# fpga-power.net
KiCad netlist of a schematic drawn in Altium Designer
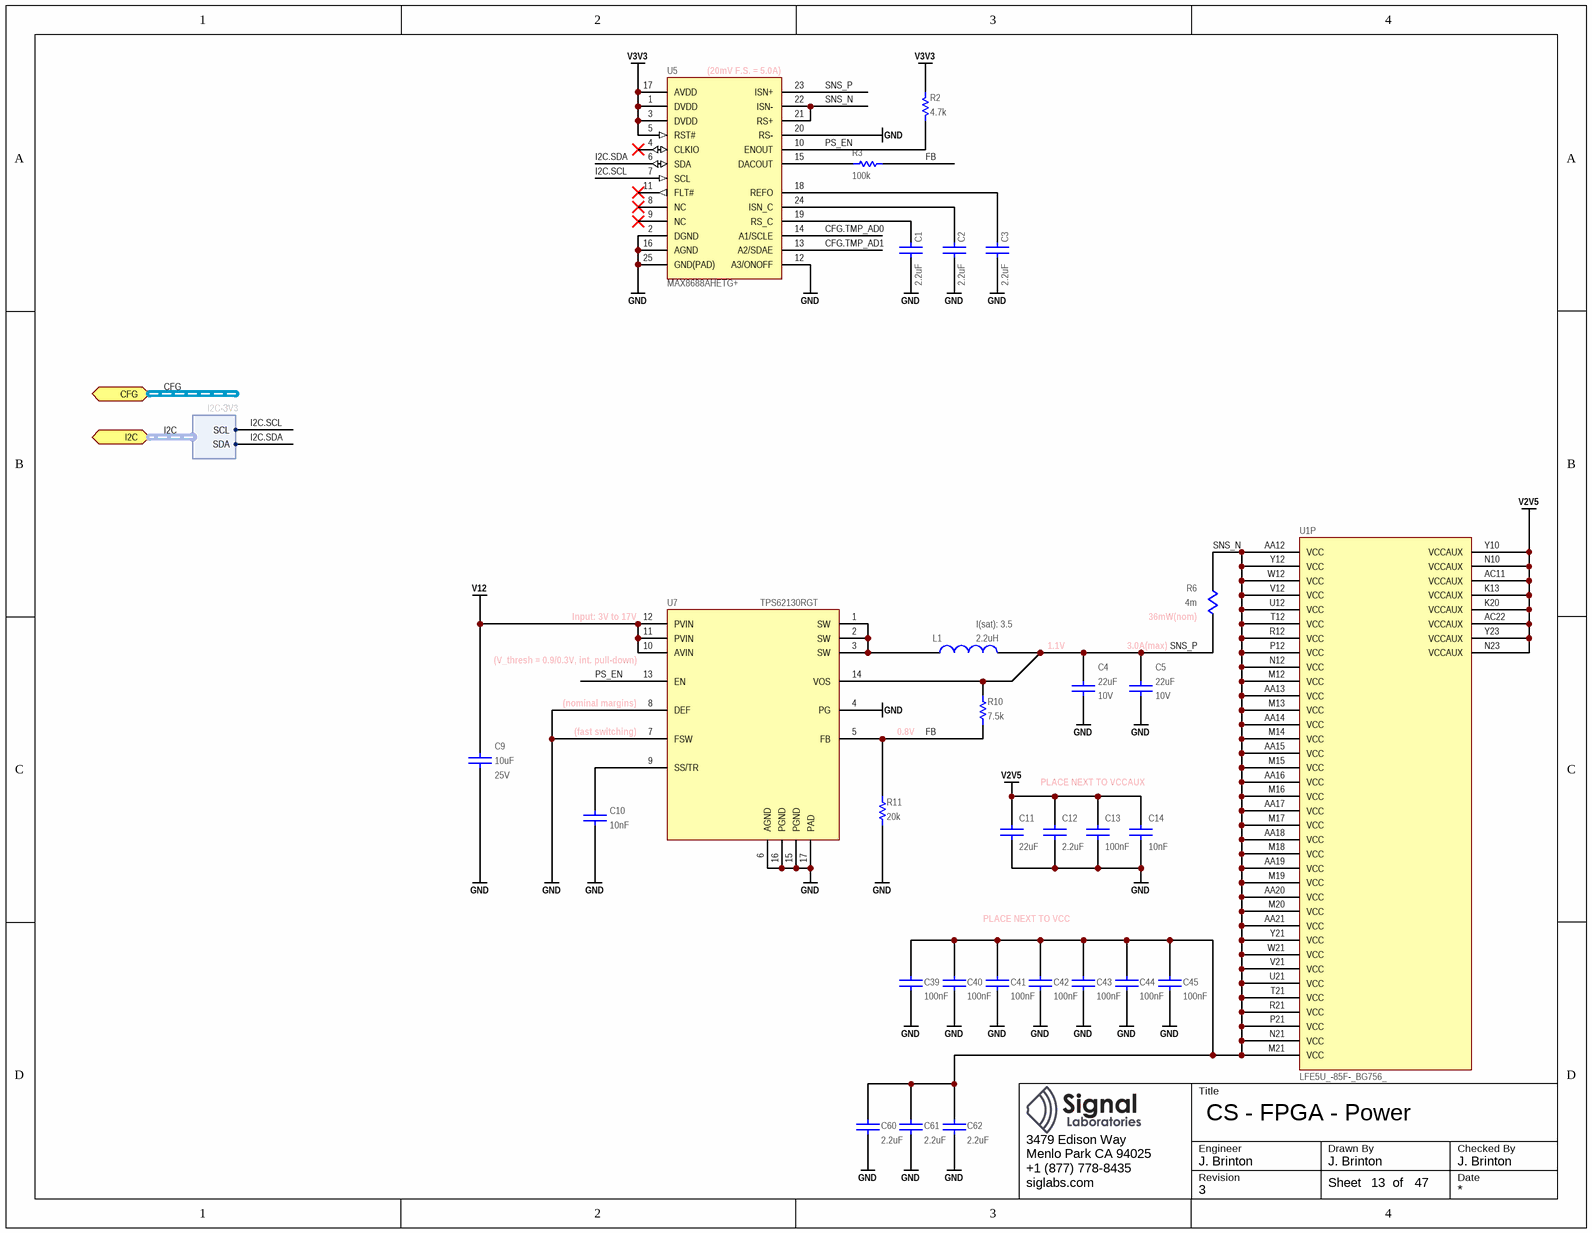
[diagram p0: fpga-power.SchDoc]

(export (version "E")
  (design (tool "Eeschema 10.0.6"))
  (components
    (comp (ref "C1")
      (value "2.2uF")
      (footprint "CAPC160X80X90L20N")
      (description "Ceramic Capacitor 2.2uF ±20% 10V X7R 0603")
      (fields (field (name "MANUFACTURER") "TDK") (field (name "TOLERANCE") "±20%"))
      (libsource (lib "generic") (part "CAP"))
    )
    (comp (ref "C2")
      (value "2.2uF")
      (footprint "CAPC160X80X90L20N")
      (description "Ceramic Capacitor 2.2uF ±20% 10V X7R 0603")
      (fields (field (name "MANUFACTURER") "TDK") (field (name "TOLERANCE") "±20%"))
      (libsource (lib "generic") (part "CAP"))
    )
    (comp (ref "C3")
      (value "2.2uF")
      (footprint "CAPC160X80X90L20N")
      (description "Ceramic Capacitor 2.2uF ±20% 10V X7R 0603")
      (fields (field (name "MANUFACTURER") "TDK") (field (name "TOLERANCE") "±20%"))
      (libsource (lib "generic") (part "CAP"))
    )
    (comp (ref "C4")
      (value "22uF")
      (footprint "CAPC200X125X145L45N")
      (description "Ceramic Capacitor 22uF ±20% 10V X7S 0805")
      (fields
        (field (name "MANUFACTURER") "TDK")
        (field (name "TOLERANCE") "±20%")
        (field (name "VOLTAGE") "10V")
      )
      (libsource (lib "generic") (part "CAP"))
    )
    (comp (ref "C5")
      (value "22uF")
      (footprint "CAPC200X125X145L45N")
      (description "Ceramic Capacitor 22uF ±20% 10V X7S 0805")
      (fields
        (field (name "MANUFACTURER") "TDK")
        (field (name "TOLERANCE") "±20%")
        (field (name "VOLTAGE") "10V")
      )
      (libsource (lib "generic") (part "CAP"))
    )
    (comp (ref "C9")
      (value "10uF")
      (footprint "CAPC200X125X145L45N")
      (description "Ceramic Capacitor 10uF ±10% 25V X6S 0805")
      (fields
        (field (name "MANUFACTURER") "Murata")
        (field (name "TOLERANCE") "±10%")
        (field (name "VOLTAGE") "25V")
      )
      (libsource (lib "") (part "CAP_1"))
    )
    (comp (ref "C10")
      (value "10nF")
      (footprint "CAPC100X50X55L25N")
      (description "Ceramic Capacitor 10nF ±10% 50V X7R 0402")
      (fields (field (name "MANUFACTURER") "Murata") (field (name "TOLERANCE") "±10%"))
      (libsource (lib "") (part "CAP_1"))
    )
    (comp (ref "C11")
      (value "22uF")
      (footprint "CAPC200X125X145L45N")
      (description "Ceramic Capacitor 22uF ±20% 10V X7S 0805")
      (fields (field (name "MANUFACTURER") "TDK") (field (name "TOLERANCE") "±20%"))
      (libsource (lib "generic") (part "CAP"))
    )
    (comp (ref "C12")
      (value "2.2uF")
      (footprint "CAPC160X80X90L20N")
      (description "Ceramic Capacitor 2.2uF ±20% 10V X7R 0603")
      (fields (field (name "MANUFACTURER") "TDK") (field (name "TOLERANCE") "±20%"))
      (libsource (lib "generic") (part "CAP"))
    )
    (comp (ref "C13")
      (value "100nF")
      (footprint "CAPC100X50X55L25N")
      (description "Ceramic Capacitor 100nF ±10% 50V X7R 0402")
      (fields (field (name "MANUFACTURER") "Murata") (field (name "TOLERANCE") "±10%"))
      (libsource (lib "generic") (part "CAP"))
    )
    (comp (ref "C14")
      (value "10nF")
      (footprint "CAPC100X50X55L25N")
      (description "Ceramic Capacitor 10nF ±10% 50V X7R 0402")
      (fields (field (name "MANUFACTURER") "Murata") (field (name "TOLERANCE") "±10%"))
      (libsource (lib "") (part "CAP_1"))
    )
    (comp (ref "C39")
      (value "100nF")
      (footprint "CAPC100X50X55L25N")
      (description "Ceramic Capacitor 100nF ±10% 50V X7R 0402")
      (fields (field (name "MANUFACTURER") "Murata") (field (name "TOLERANCE") "±10%"))
      (libsource (lib "generic") (part "CAP"))
    )
    (comp (ref "C40")
      (value "100nF")
      (footprint "CAPC100X50X55L25N")
      (description "Ceramic Capacitor 100nF ±10% 50V X7R 0402")
      (fields (field (name "MANUFACTURER") "Murata") (field (name "TOLERANCE") "±10%"))
      (libsource (lib "generic") (part "CAP"))
    )
    (comp (ref "C41")
      (value "100nF")
      (footprint "CAPC100X50X55L25N")
      (description "Ceramic Capacitor 100nF ±10% 50V X7R 0402")
      (fields (field (name "MANUFACTURER") "Murata") (field (name "TOLERANCE") "±10%"))
      (libsource (lib "generic") (part "CAP"))
    )
    (comp (ref "C42")
      (value "100nF")
      (footprint "CAPC100X50X55L25N")
      (description "Ceramic Capacitor 100nF ±10% 50V X7R 0402")
      (fields (field (name "MANUFACTURER") "Murata") (field (name "TOLERANCE") "±10%"))
      (libsource (lib "generic") (part "CAP"))
    )
    (comp (ref "C43")
      (value "100nF")
      (footprint "CAPC100X50X55L25N")
      (description "Ceramic Capacitor 100nF ±10% 50V X7R 0402")
      (fields (field (name "MANUFACTURER") "Murata") (field (name "TOLERANCE") "±10%"))
      (libsource (lib "generic") (part "CAP"))
    )
    (comp (ref "C44")
      (value "100nF")
      (footprint "CAPC100X50X55L25N")
      (description "Ceramic Capacitor 100nF ±10% 50V X7R 0402")
      (fields (field (name "MANUFACTURER") "Murata") (field (name "TOLERANCE") "±10%"))
      (libsource (lib "generic") (part "CAP"))
    )
    (comp (ref "C45")
      (value "100nF")
      (footprint "CAPC100X50X55L25N")
      (description "Ceramic Capacitor 100nF ±10% 50V X7R 0402")
      (fields (field (name "MANUFACTURER") "Murata") (field (name "TOLERANCE") "±10%"))
      (libsource (lib "generic") (part "CAP"))
    )
    (comp (ref "C60")
      (value "2.2uF")
      (footprint "CAPC160X80X90L20N")
      (description "Ceramic Capacitor 2.2uF ±20% 10V X7R 0603")
      (fields (field (name "MANUFACTURER") "TDK") (field (name "TOLERANCE") "±20%"))
      (libsource (lib "generic") (part "CAP"))
    )
    (comp (ref "C61")
      (value "2.2uF")
      (footprint "CAPC160X80X90L20N")
      (description "Ceramic Capacitor 2.2uF ±20% 10V X7R 0603")
      (fields (field (name "MANUFACTURER") "TDK") (field (name "TOLERANCE") "±20%"))
      (libsource (lib "generic") (part "CAP"))
    )
    (comp (ref "C62")
      (value "2.2uF")
      (footprint "CAPC160X80X90L20N")
      (description "Ceramic Capacitor 2.2uF ±20% 10V X7R 0603")
      (fields (field (name "MANUFACTURER") "TDK") (field (name "TOLERANCE") "±20%"))
      (libsource (lib "generic") (part "CAP"))
    )
    (comp (ref "L1")
      (value "2.2uH")
      (footprint "coilcraft:XFL4020")
      (description "Wirewound Inductor 2.2uH +/-20% 3.5A SMD")
      (fields
        (field (name "MANUFACTURER") "Coilcraft")
        (field (name "I(SAT)") "3.5")
        (field (name "Comment") "XFL4020-222ME")
      )
      (libsource (lib "CamBoard_Pico_70.19K") (part "COIL"))
    )
    (comp (ref "R2")
      (value "4.7k")
      (footprint "RESC1005X40N")
      (description "Thick Film Resistor 4.7k ±1% 0.1W 75V 0402")
      (fields (field (name "TOLERANCE") "±1%") (field (name "MANUFACTURER") "Panasonic"))
      (libsource (lib "generic") (part "RES"))
    )
    (comp (ref "R3")
      (value "100k")
      (footprint "RESC1005X40N")
      (description "Thick Film Resistor 100k ±1% 0.1W 50V 0402")
      (fields (field (name "MANUFACTURER") "Panasonic") (field (name "TOLERANCE") "±1%"))
      (libsource (lib "generic") (part "RES"))
    )
    (comp (ref "R6")
      (value "4m")
      (footprint "RESC3216X80L110N")
      (description "Current Sense Resistor 4mOhm +/-1% SMD 1206")
      (fields (field (name "MANUFACTURER") "Riedon") (field (name "Comment") "CSR1206-0R004F1"))
      (libsource (lib "Kron Library Rev 3") (part "CSR1206-0R001F1"))
    )
    (comp (ref "R10")
      (value "7.5k")
      (footprint "RESC2012X70N")
      (description "Thin Film Resistor 7.5k ±0.1% 0.125W 100V 0805")
      (fields (field (name "TOLERANCE") "±0.1%") (field (name "MANUFACTURER") "Panasonic"))
      (libsource (lib "generic") (part "RES"))
    )
    (comp (ref "R11")
      (value "20k")
      (footprint "RESC2012X70N")
      (description "Thin Film Resistor 20k ±0.1% 0.125W 100V 0805")
      (fields (field (name "TOLERANCE") "±0.1%") (field (name "MANUFACTURER") "Panasonic"))
      (libsource (lib "generic") (part "RES"))
    )
    (comp (ref "U1")
      (value "LFE5U_-85F-_BG756_")
      (footprint "lattice:caBGA756")
      (description "ECP5 FPGA, 85k LUT, 756-caBGA")
      (fields (field (name "MANUFACTURER") "Lattice Semiconductor"))
      (libsource (lib "lattice") (part "LFE5U_-85F-_BG756_"))
    )
    (comp (ref "U5")
      (value "MAX8688AHETG+")
      (footprint "generic:QFN25P50_400X400X80L40X24T260N")
      (description "Digital Power-Supply Controller/Monitor")
      (fields (field (name "MANUFACTURER") "Maxim Integrated"))
      (libsource (lib "maxim") (part "MAX8688AHETG+"))
    )
    (comp (ref "U7")
      (value "TPS62130RGT")
      (footprint "S-PQFP-8N_NOVIA")
      (description "3-17V 3A Step-Down Converter VQFN")
      (fields (field (name "MANUFACTURER") "Texas Instruments"))
      (libsource (lib "ti") (part "TPS62130RGT"))
    )
  )
  (nets
    (net (code "3") (name "/CFG.TMP_AD0") (class "Default")
      (node (ref "U5") (pin "14") (pinfunction "A1/SCLE_14") (pintype "passive"))
    )
    (net (code "4") (name "/CFG.TMP_AD1") (class "Default")
      (node (ref "U5") (pin "13") (pinfunction "A2/SDAE_13") (pintype "passive"))
    )
    (net (code "5") (name "/FB") (class "Default")
      (node (ref "R10") (pin "1") (pinfunction "1_1") (pintype "passive"))
      (node (ref "R11") (pin "2") (pinfunction "2_2") (pintype "passive"))
      (node (ref "R3") (pin "2") (pinfunction "2_2") (pintype "passive"))
      (node (ref "U7") (pin "5") (pinfunction "FB_5") (pintype "passive"))
    )
    (net (code "6") (name "/I2C.SCL") (class "Default")
      (node (ref "U5") (pin "7") (pinfunction "SCL_7") (pintype "input"))
    )
    (net (code "7") (name "/I2C.SDA") (class "Default")
      (node (ref "U5") (pin "6") (pinfunction "SDA_6") (pintype "bidirectional"))
    )
    (net (code "9") (name "/PS_EN") (class "Default")
      (node (ref "R2") (pin "1") (pinfunction "1_1") (pintype "passive"))
      (node (ref "U5") (pin "10") (pinfunction "ENOUT_10") (pintype "passive"))
      (node (ref "U7") (pin "13") (pinfunction "EN_13") (pintype "passive"))
    )
    (net (code "10") (name "/SNS_N") (class "Default")
      (node (ref "C39") (pin "2") (pinfunction "2_2") (pintype "passive"))
      (node (ref "C40") (pin "2") (pinfunction "2_2") (pintype "passive"))
      (node (ref "C41") (pin "2") (pinfunction "2_2") (pintype "passive"))
      (node (ref "C42") (pin "2") (pinfunction "2_2") (pintype "passive"))
      (node (ref "C43") (pin "2") (pinfunction "2_2") (pintype "passive"))
      (node (ref "C44") (pin "2") (pinfunction "2_2") (pintype "passive"))
      (node (ref "C45") (pin "2") (pinfunction "2_2") (pintype "passive"))
      (node (ref "C60") (pin "2") (pinfunction "2_2") (pintype "passive"))
      (node (ref "C61") (pin "2") (pinfunction "2_2") (pintype "passive"))
      (node (ref "C62") (pin "2") (pinfunction "2_2") (pintype "passive"))
      (node (ref "R6") (pin "2") (pintype "passive"))
      (node (ref "U1") (pin "AA12") (pinfunction "VCC_AA12") (pintype "power_in"))
      (node (ref "U1") (pin "AA13") (pinfunction "VCC_AA13") (pintype "power_in"))
      (node (ref "U1") (pin "AA14") (pinfunction "VCC_AA14") (pintype "power_in"))
      (node (ref "U1") (pin "AA15") (pinfunction "VCC_AA15") (pintype "power_in"))
      (node (ref "U1") (pin "AA16") (pinfunction "VCC_AA16") (pintype "power_in"))
      (node (ref "U1") (pin "AA17") (pinfunction "VCC_AA17") (pintype "power_in"))
      (node (ref "U1") (pin "AA18") (pinfunction "VCC_AA18") (pintype "power_in"))
      (node (ref "U1") (pin "AA19") (pinfunction "VCC_AA19") (pintype "power_in"))
      (node (ref "U1") (pin "AA20") (pinfunction "VCC_AA20") (pintype "power_in"))
      (node (ref "U1") (pin "AA21") (pinfunction "VCC_AA21") (pintype "power_in"))
      (node (ref "U1") (pin "M12") (pinfunction "VCC_M12") (pintype "power_in"))
      (node (ref "U1") (pin "M13") (pinfunction "VCC_M13") (pintype "power_in"))
      (node (ref "U1") (pin "M14") (pinfunction "VCC_M14") (pintype "power_in"))
      (node (ref "U1") (pin "M15") (pinfunction "VCC_M15") (pintype "power_in"))
      (node (ref "U1") (pin "M16") (pinfunction "VCC_M16") (pintype "power_in"))
      (node (ref "U1") (pin "M17") (pinfunction "VCC_M17") (pintype "power_in"))
      (node (ref "U1") (pin "M18") (pinfunction "VCC_M18") (pintype "power_in"))
      (node (ref "U1") (pin "M19") (pinfunction "VCC_M19") (pintype "power_in"))
      (node (ref "U1") (pin "M20") (pinfunction "VCC_M20") (pintype "power_in"))
      (node (ref "U1") (pin "M21") (pinfunction "VCC_M21") (pintype "power_in"))
      (node (ref "U1") (pin "N12") (pinfunction "VCC_N12") (pintype "power_in"))
      (node (ref "U1") (pin "N21") (pinfunction "VCC_N21") (pintype "power_in"))
      (node (ref "U1") (pin "P12") (pinfunction "VCC_P12") (pintype "power_in"))
      (node (ref "U1") (pin "P21") (pinfunction "VCC_P21") (pintype "power_in"))
      (node (ref "U1") (pin "R12") (pinfunction "VCC_R12") (pintype "power_in"))
      (node (ref "U1") (pin "R21") (pinfunction "VCC_R21") (pintype "power_in"))
      (node (ref "U1") (pin "T12") (pinfunction "VCC_T12") (pintype "power_in"))
      (node (ref "U1") (pin "T21") (pinfunction "VCC_T21") (pintype "power_in"))
      (node (ref "U1") (pin "U12") (pinfunction "VCC_U12") (pintype "power_in"))
      (node (ref "U1") (pin "U21") (pinfunction "VCC_U21") (pintype "power_in"))
      (node (ref "U1") (pin "V12") (pinfunction "VCC_V12") (pintype "power_in"))
      (node (ref "U1") (pin "V21") (pinfunction "VCC_V21") (pintype "power_in"))
      (node (ref "U1") (pin "W12") (pinfunction "VCC_W12") (pintype "power_in"))
      (node (ref "U1") (pin "W21") (pinfunction "VCC_W21") (pintype "power_in"))
      (node (ref "U1") (pin "Y12") (pinfunction "VCC_Y12") (pintype "power_in"))
      (node (ref "U1") (pin "Y21") (pinfunction "VCC_Y21") (pintype "power_in"))
      (node (ref "U5") (pin "21") (pinfunction "RS+_21") (pintype "passive"))
      (node (ref "U5") (pin "22") (pinfunction "ISN-_22") (pintype "passive"))
    )
    (net (code "11") (name "/SNS_P") (class "Default")
      (node (ref "C4") (pin "2") (pinfunction "2_2") (pintype "passive"))
      (node (ref "C5") (pin "2") (pinfunction "2_2") (pintype "passive"))
      (node (ref "L1") (pin "2") (pinfunction "2_2") (pintype "passive"))
      (node (ref "R10") (pin "2") (pinfunction "2_2") (pintype "passive"))
      (node (ref "R6") (pin "1") (pintype "passive"))
      (node (ref "U5") (pin "23") (pinfunction "ISN+_23") (pintype "passive"))
      (node (ref "U7") (pin "14") (pinfunction "VOS_14") (pintype "passive"))
    )
    (net (code "13") (name "GND") (class "Default")
      (node (ref "C1") (pin "1") (pinfunction "1_1") (pintype "passive"))
      (node (ref "C10") (pin "2") (pinfunction "2_2") (pintype "passive"))
      (node (ref "C11") (pin "1") (pinfunction "1_1") (pintype "passive"))
      (node (ref "C12") (pin "1") (pinfunction "1_1") (pintype "passive"))
      (node (ref "C13") (pin "1") (pinfunction "1_1") (pintype "passive"))
      (node (ref "C14") (pin "2") (pinfunction "2_2") (pintype "passive"))
      (node (ref "C2") (pin "1") (pinfunction "1_1") (pintype "passive"))
      (node (ref "C3") (pin "1") (pinfunction "1_1") (pintype "passive"))
      (node (ref "C39") (pin "1") (pinfunction "1_1") (pintype "passive"))
      (node (ref "C4") (pin "1") (pinfunction "1_1") (pintype "passive"))
      (node (ref "C40") (pin "1") (pinfunction "1_1") (pintype "passive"))
      (node (ref "C41") (pin "1") (pinfunction "1_1") (pintype "passive"))
      (node (ref "C42") (pin "1") (pinfunction "1_1") (pintype "passive"))
      (node (ref "C43") (pin "1") (pinfunction "1_1") (pintype "passive"))
      (node (ref "C44") (pin "1") (pinfunction "1_1") (pintype "passive"))
      (node (ref "C45") (pin "1") (pinfunction "1_1") (pintype "passive"))
      (node (ref "C5") (pin "1") (pinfunction "1_1") (pintype "passive"))
      (node (ref "C60") (pin "1") (pinfunction "1_1") (pintype "passive"))
      (node (ref "C61") (pin "1") (pinfunction "1_1") (pintype "passive"))
      (node (ref "C62") (pin "1") (pinfunction "1_1") (pintype "passive"))
      (node (ref "C9") (pin "1") (pinfunction "1_1") (pintype "passive"))
      (node (ref "R11") (pin "1") (pinfunction "1_1") (pintype "passive"))
      (node (ref "U5") (pin "12") (pinfunction "A3/ONOFF_12") (pintype "passive"))
      (node (ref "U5") (pin "16") (pinfunction "AGND_16") (pintype "power_in"))
      (node (ref "U5") (pin "2") (pinfunction "DGND_2") (pintype "power_in"))
      (node (ref "U5") (pin "20") (pinfunction "RS-_20") (pintype "passive"))
      (node (ref "U5") (pin "25") (pinfunction "GND(PAD)_25") (pintype "power_in"))
      (node (ref "U7") (pin "15") (pinfunction "PGND_15") (pintype "passive"))
      (node (ref "U7") (pin "16") (pinfunction "PGND_16") (pintype "passive"))
      (node (ref "U7") (pin "17") (pinfunction "PAD_17") (pintype "passive"))
      (node (ref "U7") (pin "4") (pinfunction "PG_4") (pintype "passive"))
      (node (ref "U7") (pin "6") (pinfunction "AGND_6") (pintype "passive"))
      (node (ref "U7") (pin "7") (pinfunction "FSW_7") (pintype "passive"))
      (node (ref "U7") (pin "8") (pinfunction "DEF_8") (pintype "passive"))
    )
    (net (code "14") (name "Net-(L1-Pad1)") (class "Default")
      (node (ref "L1") (pin "1") (pinfunction "1_1") (pintype "passive"))
      (node (ref "U7") (pin "1") (pinfunction "SW_1") (pintype "passive"))
      (node (ref "U7") (pin "2") (pinfunction "SW_2") (pintype "passive"))
      (node (ref "U7") (pin "3") (pinfunction "SW_3") (pintype "passive"))
    )
    (net (code "15") (name "Net-(U5-DACOUT)") (class "Default")
      (node (ref "R3") (pin "1") (pinfunction "1_1") (pintype "passive"))
      (node (ref "U5") (pin "15") (pinfunction "DACOUT_15") (pintype "passive"))
    )
    (net (code "16") (name "Net-(U5-ISN_C)") (class "Default")
      (node (ref "C2") (pin "2") (pinfunction "2_2") (pintype "passive"))
      (node (ref "U5") (pin "24") (pinfunction "ISN_C_24") (pintype "passive"))
    )
    (net (code "17") (name "Net-(U5-REFO)") (class "Default")
      (node (ref "C3") (pin "2") (pinfunction "2_2") (pintype "passive"))
      (node (ref "U5") (pin "18") (pinfunction "REFO_18") (pintype "passive"))
    )
    (net (code "18") (name "Net-(U5-RS_C)") (class "Default")
      (node (ref "C1") (pin "2") (pinfunction "2_2") (pintype "passive"))
      (node (ref "U5") (pin "19") (pinfunction "RS_C_19") (pintype "passive"))
    )
    (net (code "19") (name "Net-(U7-SS{slash}TR)") (class "Default")
      (node (ref "C10") (pin "1") (pinfunction "1_1") (pintype "passive"))
      (node (ref "U7") (pin "9") (pinfunction "SS/TR_9") (pintype "passive"))
    )
    (net (code "20") (name "V2V5") (class "Default")
      (node (ref "C11") (pin "2") (pinfunction "2_2") (pintype "passive"))
      (node (ref "C12") (pin "2") (pinfunction "2_2") (pintype "passive"))
      (node (ref "C13") (pin "2") (pinfunction "2_2") (pintype "passive"))
      (node (ref "C14") (pin "1") (pinfunction "1_1") (pintype "passive"))
      (node (ref "U1") (pin "AC11") (pinfunction "VCCAUX_AC11") (pintype "power_in"))
      (node (ref "U1") (pin "AC22") (pinfunction "VCCAUX_AC22") (pintype "power_in"))
      (node (ref "U1") (pin "K13") (pinfunction "VCCAUX_K13") (pintype "power_in"))
      (node (ref "U1") (pin "K20") (pinfunction "VCCAUX_K20") (pintype "power_in"))
      (node (ref "U1") (pin "N10") (pinfunction "VCCAUX_N10") (pintype "power_in"))
      (node (ref "U1") (pin "N23") (pinfunction "VCCAUX_N23") (pintype "power_in"))
      (node (ref "U1") (pin "Y10") (pinfunction "VCCAUX_Y10") (pintype "power_in"))
      (node (ref "U1") (pin "Y23") (pinfunction "VCCAUX_Y23") (pintype "power_in"))
    )
    (net (code "21") (name "V3V3") (class "Default")
      (node (ref "R2") (pin "2") (pinfunction "2_2") (pintype "passive"))
      (node (ref "U5") (pin "1") (pinfunction "DVDD_1") (pintype "power_in"))
      (node (ref "U5") (pin "17") (pinfunction "AVDD_17") (pintype "power_in"))
      (node (ref "U5") (pin "3") (pinfunction "DVDD_3") (pintype "power_in"))
      (node (ref "U5") (pin "5") (pinfunction "RST#_5") (pintype "input"))
    )
    (net (code "22") (name "V12") (class "Default")
      (node (ref "C9") (pin "2") (pinfunction "2_2") (pintype "passive"))
      (node (ref "U7") (pin "10") (pinfunction "AVIN_10") (pintype "passive"))
      (node (ref "U7") (pin "11") (pinfunction "PVIN_11") (pintype "passive"))
      (node (ref "U7") (pin "12") (pinfunction "PVIN_12") (pintype "passive"))
    )
    (net (code "23") (name "unconnected-(U5-CLKIO-Pad4)") (class "Default")
      (node (ref "U5") (pin "4") (pinfunction "CLKIO_4") (pintype "bidirectional+no_connect"))
    )
    (net (code "24") (name "unconnected-(U5-FLT#-Pad11)") (class "Default")
      (node (ref "U5") (pin "11") (pinfunction "FLT#_11") (pintype "output+no_connect"))
    )
    (net (code "25") (name "unconnected-(U5-NC-Pad8)") (class "Default")
      (node (ref "U5") (pin "8") (pinfunction "NC_8") (pintype "passive+no_connect"))
    )
    (net (code "26") (name "unconnected-(U5-NC-Pad9)") (class "Default")
      (node (ref "U5") (pin "9") (pinfunction "NC_9") (pintype "passive+no_connect"))
    )
  )
)
